# Schematic_EasyEDA.net
KiCad netlist of a schematic drawn in EasyEDA
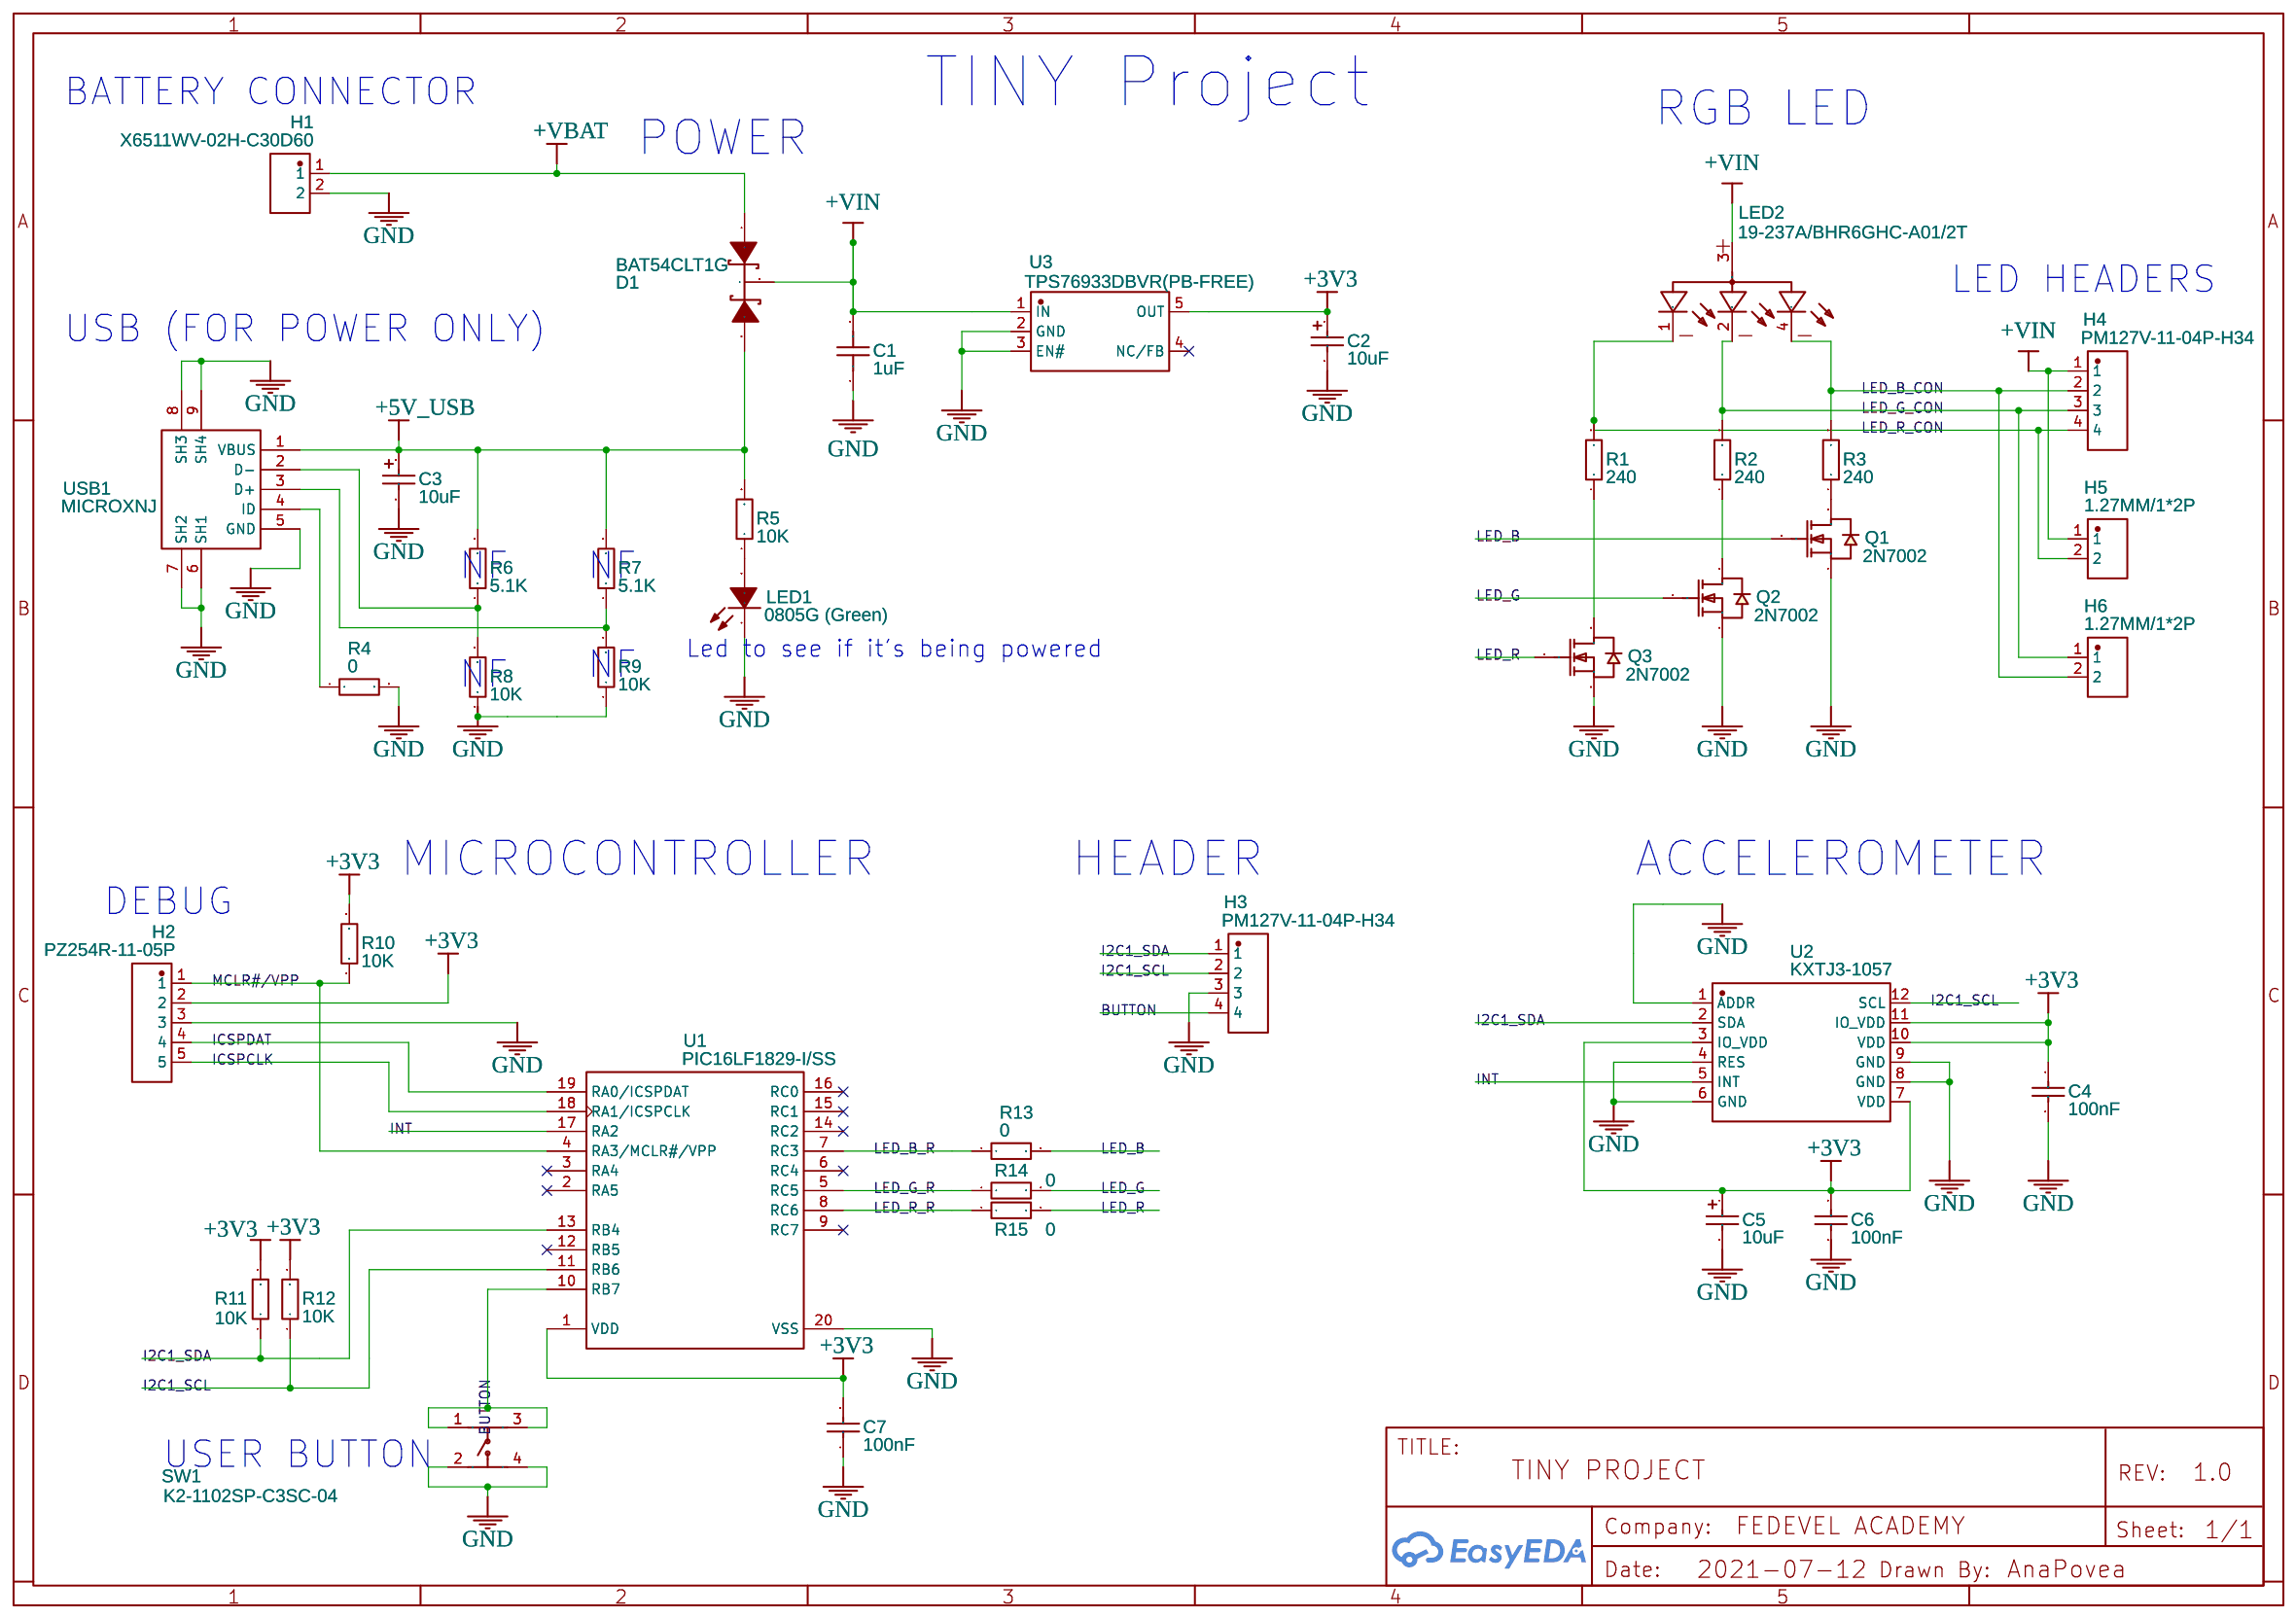
[diagram p0: schematic sheet]

(export (version "E")
  (design (tool "Eeschema 10.0.6"))
  (components
    (comp (ref "C1")
      (value "1uF")
      (fields
        (field (name "BOM_Manufacturer Part") "CL05A105KA5NQNC")
        (field (name "BOM_Supplier Part") "C52923")
      )
      (libsource (lib "") (part "CL05A105KA5NQNC"))
    )
    (comp (ref "C2")
      (value "10uF")
      (fields
        (field (name "BOM_Manufacturer Part") "TAJA106K016RNJ")
        (field (name "BOM_Supplier Part") "C7171")
      )
      (libsource (lib "") (part "TAJA106K016RNJ"))
    )
    (comp (ref "C3")
      (value "10uF")
      (fields
        (field (name "BOM_Manufacturer Part") "TAJA106K016RNJ")
        (field (name "BOM_Supplier Part") "C7171")
      )
      (libsource (lib "") (part "TAJA106K016RNJ"))
    )
    (comp (ref "C4")
      (value "100nF")
      (fields
        (field (name "BOM_Manufacturer Part") "CL05B104KO5NNNC")
        (field (name "BOM_Supplier Part") "C1525")
      )
      (libsource (lib "") (part "CL05B104KO5NNNC"))
    )
    (comp (ref "C5")
      (value "10uF")
      (fields
        (field (name "BOM_Manufacturer Part") "TAJA106K016RNJ")
        (field (name "BOM_Supplier Part") "C7171")
      )
      (libsource (lib "") (part "TAJA106K016RNJ"))
    )
    (comp (ref "C6")
      (value "100nF")
      (fields
        (field (name "BOM_Manufacturer Part") "CL05B104KO5NNNC")
        (field (name "BOM_Supplier Part") "C1525")
      )
      (libsource (lib "") (part "CL05B104KO5NNNC"))
    )
    (comp (ref "C7")
      (value "100nF")
      (fields
        (field (name "BOM_Manufacturer Part") "CL05B104KO5NNNC")
        (field (name "BOM_Supplier Part") "C1525")
      )
      (libsource (lib "") (part "CL05B104KO5NNNC"))
    )
    (comp (ref "D1")
      (value "BAT54CLT1G")
      (fields (field (name "BOM_Supplier Part") "C14308"))
      (libsource (lib "") (part "BAT54CLT1G"))
    )
    (comp (ref "H1")
      (value "X6511WV-02H-C30D60")
      (fields (field (name "BOM_Supplier Part") "C706874"))
      (libsource (lib "") (part "X6511WV-02H-C30D60"))
    )
    (comp (ref "H2")
      (value "PZ254R-11-05P")
      (fields (field (name "BOM_Supplier Part") "C492413"))
      (libsource (lib "") (part "PZ254R-11-05P"))
    )
    (comp (ref "H3")
      (value "PM127V-11-04P-H34")
      (fields (field (name "BOM_Supplier Part") "C492398"))
      (libsource (lib "") (part "PM127V-11-04P-H34"))
    )
    (comp (ref "H4")
      (value "PM127V-11-04P-H34")
      (fields (field (name "BOM_Supplier Part") "C492398"))
      (libsource (lib "") (part "PM127V-11-04P-H34"))
    )
    (comp (ref "H5")
      (value "1.27MM/1*2P")
      (fields
        (field (name "BOM_Manufacturer Part") "1.27mm/1*2P")
        (field (name "BOM_Supplier Part") "C703015")
      )
      (libsource (lib "") (part "1.27MM/1*2P"))
    )
    (comp (ref "H6")
      (value "1.27MM/1*2P")
      (fields
        (field (name "BOM_Manufacturer Part") "1.27mm/1*2P")
        (field (name "BOM_Supplier Part") "C703015")
      )
      (libsource (lib "") (part "1.27MM/1*2P"))
    )
    (comp (ref "LED1")
      (value "0805G (Green)")
      (fields (field (name "BOM_Supplier Part") "C2297"))
      (libsource (lib "") (part "0805G (Green)"))
    )
    (comp (ref "LED2")
      (value "19-237A/BHR6GHC-A01/2T")
      (fields (field (name "BOM_Supplier Part") "C114830"))
      (libsource (lib "") (part "19-237A/BHR6GHC-A01/2T"))
    )
    (comp (ref "Q1")
      (value "2N7002")
      (fields (field (name "BOM_Supplier Part") "C8545"))
      (libsource (lib "") (part "2N7002"))
    )
    (comp (ref "Q2")
      (value "2N7002")
      (fields (field (name "BOM_Supplier Part") "C8545"))
      (libsource (lib "") (part "2N7002"))
    )
    (comp (ref "Q3")
      (value "2N7002")
      (fields (field (name "BOM_Supplier Part") "C8545"))
      (libsource (lib "") (part "2N7002"))
    )
    (comp (ref "R1")
      (value "240")
      (fields
        (field (name "BOM_Manufacturer Part") "0402WGF2400TCE")
        (field (name "BOM_Supplier Part") "C25094")
      )
      (libsource (lib "") (part "0402WGF2400TCE"))
    )
    (comp (ref "R2")
      (value "240")
      (fields
        (field (name "BOM_Manufacturer Part") "0402WGF2400TCE")
        (field (name "BOM_Supplier Part") "C25094")
      )
      (libsource (lib "") (part "0402WGF2400TCE"))
    )
    (comp (ref "R3")
      (value "240")
      (fields
        (field (name "BOM_Manufacturer Part") "0402WGF2400TCE")
        (field (name "BOM_Supplier Part") "C25094")
      )
      (libsource (lib "") (part "0402WGF2400TCE"))
    )
    (comp (ref "R4")
      (value "0")
      (fields
        (field (name "BOM_Manufacturer Part") "0402WGF0000TCE")
        (field (name "BOM_Supplier Part") "C17168")
      )
      (libsource (lib "") (part "0402WGF0000TCE"))
    )
    (comp (ref "R5")
      (value "10K")
      (fields
        (field (name "BOM_Manufacturer Part") "0402WGF1002TCE")
        (field (name "BOM_Supplier Part") "C25744")
      )
      (libsource (lib "") (part "0402WGF1002TCE"))
    )
    (comp (ref "R6")
      (value "5.1K")
      (fields
        (field (name "BOM_Manufacturer Part") "0402WGF5101TCE")
        (field (name "BOM_Supplier Part") "C25905")
      )
      (libsource (lib "") (part "0402WGF5101TCE"))
    )
    (comp (ref "R7")
      (value "5.1K")
      (fields
        (field (name "BOM_Manufacturer Part") "0402WGF5101TCE")
        (field (name "BOM_Supplier Part") "C25905")
      )
      (libsource (lib "") (part "0402WGF5101TCE"))
    )
    (comp (ref "R8")
      (value "10K")
      (fields
        (field (name "BOM_Manufacturer Part") "0402WGF1002TCE")
        (field (name "BOM_Supplier Part") "C25744")
      )
      (libsource (lib "") (part "0402WGF1002TCE"))
    )
    (comp (ref "R9")
      (value "10K")
      (fields
        (field (name "BOM_Manufacturer Part") "0402WGF1002TCE")
        (field (name "BOM_Supplier Part") "C25744")
      )
      (libsource (lib "") (part "0402WGF1002TCE"))
    )
    (comp (ref "R10")
      (value "10K")
      (fields
        (field (name "BOM_Manufacturer Part") "0402WGF1002TCE")
        (field (name "BOM_Supplier Part") "C25744")
      )
      (libsource (lib "") (part "0402WGF1002TCE"))
    )
    (comp (ref "R11")
      (value "10K")
      (fields
        (field (name "BOM_Manufacturer Part") "0402WGF1002TCE")
        (field (name "BOM_Supplier Part") "C25744")
      )
      (libsource (lib "") (part "0402WGF1002TCE"))
    )
    (comp (ref "R12")
      (value "10K")
      (fields
        (field (name "BOM_Manufacturer Part") "0402WGF1002TCE")
        (field (name "BOM_Supplier Part") "C25744")
      )
      (libsource (lib "") (part "0402WGF1002TCE"))
    )
    (comp (ref "R13")
      (value "0")
      (fields
        (field (name "BOM_Manufacturer Part") "0402WGF0000TCE")
        (field (name "BOM_Supplier Part") "C17168")
      )
      (libsource (lib "") (part "0402WGF0000TCE"))
    )
    (comp (ref "R14")
      (value "0")
      (fields
        (field (name "BOM_Manufacturer Part") "0402WGF0000TCE")
        (field (name "BOM_Supplier Part") "C17168")
      )
      (libsource (lib "") (part "0402WGF0000TCE"))
    )
    (comp (ref "R15")
      (value "0")
      (fields
        (field (name "BOM_Manufacturer Part") "0402WGF0000TCE")
        (field (name "BOM_Supplier Part") "C17168")
      )
      (libsource (lib "") (part "0402WGF0000TCE"))
    )
    (comp (ref "SW1")
      (value "K2-1102SP-C3SC-04")
      (fields (field (name "BOM_Supplier Part") "C707347"))
      (libsource (lib "") (part "K2-1102SP-C3SC-04"))
    )
    (comp (ref "U1")
      (value "PIC16LF1829-I/SS")
      (fields (field (name "BOM_Supplier Part") "C59149"))
      (libsource (lib "") (part "PIC16LF1829-I/SS"))
    )
    (comp (ref "U2")
      (value "KXTJ3-1057")
      (fields (field (name "BOM_Supplier Part") "C442603"))
      (libsource (lib "") (part "KXTJ3-1057"))
    )
    (comp (ref "U3")
      (value "TPS76933DBVR(PB-FREE)")
      (fields (field (name "BOM_Supplier Part") "C7101"))
      (libsource (lib "") (part "TPS76933DBVR(PB-FREE)"))
    )
    (comp (ref "USB1")
      (value "MICROXNJ")
      (fields (field (name "BOM_Manufacturer Part") "MicroXNJ") (field (name "BOM_Supplier Part") "C404969"))
      (libsource (lib "") (part "MICROXNJ"))
    )
  )
  (nets
    (net (code "1") (name "+3V3") (class "Default")
      (node (ref "C2") (pin "1") (pinfunction "1_1") (pintype "input"))
      (node (ref "C4") (pin "2") (pinfunction "2_2") (pintype "input"))
      (node (ref "C5") (pin "1") (pinfunction "1_1") (pintype "input"))
      (node (ref "C6") (pin "2") (pinfunction "2_2") (pintype "input"))
      (node (ref "C7") (pin "2") (pinfunction "2_2") (pintype "input"))
      (node (ref "H2") (pin "2") (pinfunction "2_2") (pintype "unspecified"))
      (node (ref "R10") (pin "2") (pinfunction "2_2") (pintype "input"))
      (node (ref "R11") (pin "2") (pinfunction "2_2") (pintype "input"))
      (node (ref "R12") (pin "2") (pinfunction "2_2") (pintype "input"))
      (node (ref "U1") (pin "1") (pinfunction "VDD_1") (pintype "passive"))
      (node (ref "U2") (pin "10") (pinfunction "VDD_10") (pintype "unspecified"))
      (node (ref "U2") (pin "11") (pinfunction "IO_VDD_11") (pintype "unspecified"))
      (node (ref "U2") (pin "3") (pinfunction "IO_VDD_3") (pintype "unspecified"))
      (node (ref "U2") (pin "7") (pinfunction "VDD_7") (pintype "unspecified"))
      (node (ref "U3") (pin "5") (pinfunction "OUT_5") (pintype "unspecified"))
    )
    (net (code "2") (name "+5V_USB") (class "Default")
      (node (ref "C3") (pin "1") (pinfunction "1_1") (pintype "input"))
      (node (ref "D1") (pin "2") (pinfunction "A_2") (pintype "unspecified"))
      (node (ref "R5") (pin "2") (pinfunction "2_2") (pintype "input"))
      (node (ref "R6") (pin "2") (pinfunction "2_2") (pintype "input"))
      (node (ref "R7") (pin "2") (pinfunction "2_2") (pintype "input"))
      (node (ref "USB1") (pin "1") (pinfunction "VBUS_1") (pintype "unspecified"))
    )
    (net (code "3") (name "+VBAT") (class "Default")
      (node (ref "D1") (pin "1") (pinfunction "A_1") (pintype "unspecified"))
      (node (ref "H1") (pin "1") (pinfunction "1_1") (pintype "unspecified"))
    )
    (net (code "4") (name "+VIN") (class "Default")
      (node (ref "C1") (pin "2") (pinfunction "2_2") (pintype "unspecified"))
      (node (ref "D1") (pin "3") (pinfunction "K_3") (pintype "unspecified"))
      (node (ref "H4") (pin "1") (pinfunction "1_1") (pintype "unspecified"))
      (node (ref "H5") (pin "1") (pinfunction "1_1") (pintype "unspecified"))
      (node (ref "LED2") (pin "3") (pinfunction "3_3") (pintype "unspecified"))
      (node (ref "U3") (pin "1") (pinfunction "IN_1") (pintype "unspecified"))
    )
    (net (code "5") (name "/BUTTON") (class "Default")
      (node (ref "H3") (pin "4") (pinfunction "4_4") (pintype "unspecified"))
      (node (ref "SW1") (pin "1") (pinfunction "1_1") (pintype "unspecified"))
      (node (ref "SW1") (pin "3") (pinfunction "3_3") (pintype "unspecified"))
      (node (ref "U1") (pin "10") (pinfunction "RB7_10") (pintype "bidirectional"))
    )
    (net (code "6") (name "/I2C1_SCL") (class "Default")
      (node (ref "H3") (pin "2") (pinfunction "2_2") (pintype "unspecified"))
      (node (ref "R12") (pin "1") (pinfunction "1_1") (pintype "input"))
      (node (ref "U1") (pin "11") (pinfunction "RB6_11") (pintype "bidirectional"))
      (node (ref "U2") (pin "12") (pinfunction "SCL_12") (pintype "unspecified"))
    )
    (net (code "7") (name "/I2C1_SDA") (class "Default")
      (node (ref "H3") (pin "1") (pinfunction "1_1") (pintype "unspecified"))
      (node (ref "R11") (pin "1") (pinfunction "1_1") (pintype "input"))
      (node (ref "U1") (pin "13") (pinfunction "RB4_13") (pintype "bidirectional"))
      (node (ref "U2") (pin "2") (pinfunction "SDA_2") (pintype "unspecified"))
    )
    (net (code "8") (name "/ICSPCLK") (class "Default")
      (node (ref "H2") (pin "5") (pinfunction "5_5") (pintype "unspecified"))
      (node (ref "U1") (pin "18") (pinfunction "RA1/ICSPCLK_18") (pintype "bidirectional"))
    )
    (net (code "9") (name "/ICSPDAT") (class "Default")
      (node (ref "H2") (pin "4") (pinfunction "4_4") (pintype "unspecified"))
      (node (ref "U1") (pin "19") (pinfunction "RA0/ICSPDAT_19") (pintype "bidirectional"))
    )
    (net (code "10") (name "/INT") (class "Default")
      (node (ref "U1") (pin "17") (pinfunction "RA2_17") (pintype "bidirectional"))
      (node (ref "U2") (pin "5") (pinfunction "INT_5") (pintype "unspecified"))
    )
    (net (code "11") (name "/LED_B") (class "Default")
      (node (ref "Q1") (pin "1") (pinfunction "G_1") (pintype "unspecified"))
      (node (ref "R13") (pin "2") (pinfunction "2_2") (pintype "input"))
    )
    (net (code "12") (name "/LED_B_CON") (class "Default")
      (node (ref "H4") (pin "2") (pinfunction "2_2") (pintype "unspecified"))
      (node (ref "H6") (pin "2") (pinfunction "2_2") (pintype "unspecified"))
      (node (ref "LED2") (pin "4") (pinfunction "4_4") (pintype "unspecified"))
      (node (ref "R3") (pin "2") (pinfunction "2_2") (pintype "input"))
    )
    (net (code "13") (name "/LED_B_R") (class "Default")
      (node (ref "R13") (pin "1") (pinfunction "1_1") (pintype "input"))
      (node (ref "U1") (pin "7") (pinfunction "RC3_7") (pintype "bidirectional"))
    )
    (net (code "14") (name "/LED_G") (class "Default")
      (node (ref "Q2") (pin "1") (pinfunction "G_1") (pintype "unspecified"))
      (node (ref "R14") (pin "2") (pinfunction "2_2") (pintype "input"))
    )
    (net (code "15") (name "/LED_G_CON") (class "Default")
      (node (ref "H4") (pin "3") (pinfunction "3_3") (pintype "unspecified"))
      (node (ref "H6") (pin "1") (pinfunction "1_1") (pintype "unspecified"))
      (node (ref "LED2") (pin "2") (pinfunction "2_2") (pintype "unspecified"))
      (node (ref "R2") (pin "2") (pinfunction "2_2") (pintype "input"))
    )
    (net (code "16") (name "/LED_G_R") (class "Default")
      (node (ref "R14") (pin "1") (pinfunction "1_1") (pintype "input"))
      (node (ref "U1") (pin "5") (pinfunction "RC5_5") (pintype "bidirectional"))
    )
    (net (code "17") (name "/LED_R") (class "Default")
      (node (ref "Q3") (pin "1") (pinfunction "G_1") (pintype "unspecified"))
      (node (ref "R15") (pin "2") (pinfunction "2_2") (pintype "input"))
    )
    (net (code "18") (name "/LED_R_CON") (class "Default")
      (node (ref "H4") (pin "4") (pinfunction "4_4") (pintype "unspecified"))
      (node (ref "H5") (pin "2") (pinfunction "2_2") (pintype "unspecified"))
      (node (ref "LED2") (pin "1") (pinfunction "1_1") (pintype "unspecified"))
      (node (ref "R1") (pin "2") (pinfunction "2_2") (pintype "input"))
    )
    (net (code "19") (name "/LED_R_R") (class "Default")
      (node (ref "R15") (pin "1") (pinfunction "1_1") (pintype "input"))
      (node (ref "U1") (pin "8") (pinfunction "RC6_8") (pintype "bidirectional"))
    )
    (net (code "20") (name "/MCLR#{slash}VPP") (class "Default")
      (node (ref "H2") (pin "1") (pinfunction "1_1") (pintype "unspecified"))
      (node (ref "R10") (pin "1") (pinfunction "1_1") (pintype "input"))
      (node (ref "U1") (pin "4") (pinfunction "RA3/MCLR#/VPP_4") (pintype "unspecified"))
    )
    (net (code "21") (name "GND") (class "Default")
      (node (ref "C1") (pin "1") (pinfunction "1_1") (pintype "unspecified"))
      (node (ref "C2") (pin "2") (pinfunction "2_2") (pintype "input"))
      (node (ref "C3") (pin "2") (pinfunction "2_2") (pintype "input"))
      (node (ref "C4") (pin "1") (pinfunction "1_1") (pintype "input"))
      (node (ref "C5") (pin "2") (pinfunction "2_2") (pintype "input"))
      (node (ref "C6") (pin "1") (pinfunction "1_1") (pintype "input"))
      (node (ref "C7") (pin "1") (pinfunction "1_1") (pintype "input"))
      (node (ref "H1") (pin "2") (pinfunction "2_2") (pintype "unspecified"))
      (node (ref "H2") (pin "3") (pinfunction "3_3") (pintype "unspecified"))
      (node (ref "H3") (pin "3") (pinfunction "3_3") (pintype "unspecified"))
      (node (ref "LED1") (pin "1") (pinfunction "K_1") (pintype "unspecified"))
      (node (ref "Q1") (pin "2") (pinfunction "S_2") (pintype "unspecified"))
      (node (ref "Q2") (pin "2") (pinfunction "S_2") (pintype "unspecified"))
      (node (ref "Q3") (pin "2") (pinfunction "S_2") (pintype "unspecified"))
      (node (ref "R4") (pin "2") (pinfunction "2_2") (pintype "input"))
      (node (ref "R8") (pin "1") (pinfunction "1_1") (pintype "input"))
      (node (ref "R9") (pin "1") (pinfunction "1_1") (pintype "input"))
      (node (ref "SW1") (pin "2") (pinfunction "2_2") (pintype "unspecified"))
      (node (ref "SW1") (pin "4") (pinfunction "4_4") (pintype "unspecified"))
      (node (ref "U1") (pin "20") (pinfunction "VSS_20") (pintype "passive"))
      (node (ref "U2") (pin "1") (pinfunction "ADDR_1") (pintype "unspecified"))
      (node (ref "U2") (pin "4") (pinfunction "RES_4") (pintype "unspecified"))
      (node (ref "U2") (pin "6") (pinfunction "GND_6") (pintype "unspecified"))
      (node (ref "U2") (pin "8") (pinfunction "GND_8") (pintype "unspecified"))
      (node (ref "U2") (pin "9") (pinfunction "GND_9") (pintype "unspecified"))
      (node (ref "U3") (pin "2") (pinfunction "GND_2") (pintype "unspecified"))
      (node (ref "U3") (pin "3") (pinfunction "EN#_3") (pintype "unspecified"))
      (node (ref "USB1") (pin "5") (pinfunction "GND_5") (pintype "unspecified"))
      (node (ref "USB1") (pin "6") (pinfunction "SH1_6") (pintype "unspecified"))
      (node (ref "USB1") (pin "7") (pinfunction "SH2_7") (pintype "unspecified"))
      (node (ref "USB1") (pin "8") (pinfunction "SH3_8") (pintype "unspecified"))
      (node (ref "USB1") (pin "9") (pinfunction "SH4_9") (pintype "unspecified"))
    )
    (net (code "22") (name "Net-(LED1-A)") (class "Default")
      (node (ref "LED1") (pin "2") (pinfunction "A_2") (pintype "unspecified"))
      (node (ref "R5") (pin "1") (pinfunction "1_1") (pintype "input"))
    )
    (net (code "23") (name "Net-(Q1-D)") (class "Default")
      (node (ref "Q1") (pin "3") (pinfunction "D_3") (pintype "unspecified"))
      (node (ref "R3") (pin "1") (pinfunction "1_1") (pintype "input"))
    )
    (net (code "24") (name "Net-(Q2-D)") (class "Default")
      (node (ref "Q2") (pin "3") (pinfunction "D_3") (pintype "unspecified"))
      (node (ref "R2") (pin "1") (pinfunction "1_1") (pintype "input"))
    )
    (net (code "25") (name "Net-(Q3-D)") (class "Default")
      (node (ref "Q3") (pin "3") (pinfunction "D_3") (pintype "unspecified"))
      (node (ref "R1") (pin "1") (pinfunction "1_1") (pintype "input"))
    )
    (net (code "26") (name "Net-(USB1-D+)") (class "Default")
      (node (ref "R7") (pin "1") (pinfunction "1_1") (pintype "input"))
      (node (ref "R9") (pin "2") (pinfunction "2_2") (pintype "input"))
      (node (ref "USB1") (pin "3") (pinfunction "D+_3") (pintype "unspecified"))
    )
    (net (code "27") (name "Net-(USB1-D-)") (class "Default")
      (node (ref "R6") (pin "1") (pinfunction "1_1") (pintype "input"))
      (node (ref "R8") (pin "2") (pinfunction "2_2") (pintype "input"))
      (node (ref "USB1") (pin "2") (pinfunction "D-_2") (pintype "unspecified"))
    )
    (net (code "28") (name "Net-(USB1-ID)") (class "Default")
      (node (ref "R4") (pin "1") (pinfunction "1_1") (pintype "input"))
      (node (ref "USB1") (pin "4") (pinfunction "ID_4") (pintype "unspecified"))
    )
    (net (code "29") (name "unconnected-(U1-RA4-Pad3)") (class "Default")
      (node (ref "U1") (pin "3") (pinfunction "RA4_3") (pintype "bidirectional+no_connect"))
    )
    (net (code "30") (name "unconnected-(U1-RA5-Pad2)") (class "Default")
      (node (ref "U1") (pin "2") (pinfunction "RA5_2") (pintype "bidirectional+no_connect"))
    )
    (net (code "31") (name "unconnected-(U1-RB5-Pad12)") (class "Default")
      (node (ref "U1") (pin "12") (pinfunction "RB5_12") (pintype "bidirectional+no_connect"))
    )
    (net (code "32") (name "unconnected-(U1-RC0-Pad16)") (class "Default")
      (node (ref "U1") (pin "16") (pinfunction "RC0_16") (pintype "bidirectional+no_connect"))
    )
    (net (code "33") (name "unconnected-(U1-RC1-Pad15)") (class "Default")
      (node (ref "U1") (pin "15") (pinfunction "RC1_15") (pintype "bidirectional+no_connect"))
    )
    (net (code "34") (name "unconnected-(U1-RC2-Pad14)") (class "Default")
      (node (ref "U1") (pin "14") (pinfunction "RC2_14") (pintype "bidirectional+no_connect"))
    )
    (net (code "35") (name "unconnected-(U1-RC4-Pad6)") (class "Default")
      (node (ref "U1") (pin "6") (pinfunction "RC4_6") (pintype "bidirectional+no_connect"))
    )
    (net (code "36") (name "unconnected-(U1-RC7-Pad9)") (class "Default")
      (node (ref "U1") (pin "9") (pinfunction "RC7_9") (pintype "bidirectional+no_connect"))
    )
    (net (code "37") (name "unconnected-(U3-NC{slash}FB-Pad4)") (class "Default")
      (node (ref "U3") (pin "4") (pinfunction "NC/FB_4") (pintype "unspecified+no_connect"))
    )
  )
)
